# LCD-IDC_Adapter.net
KiCad netlist of a schematic drawn in EAGLE
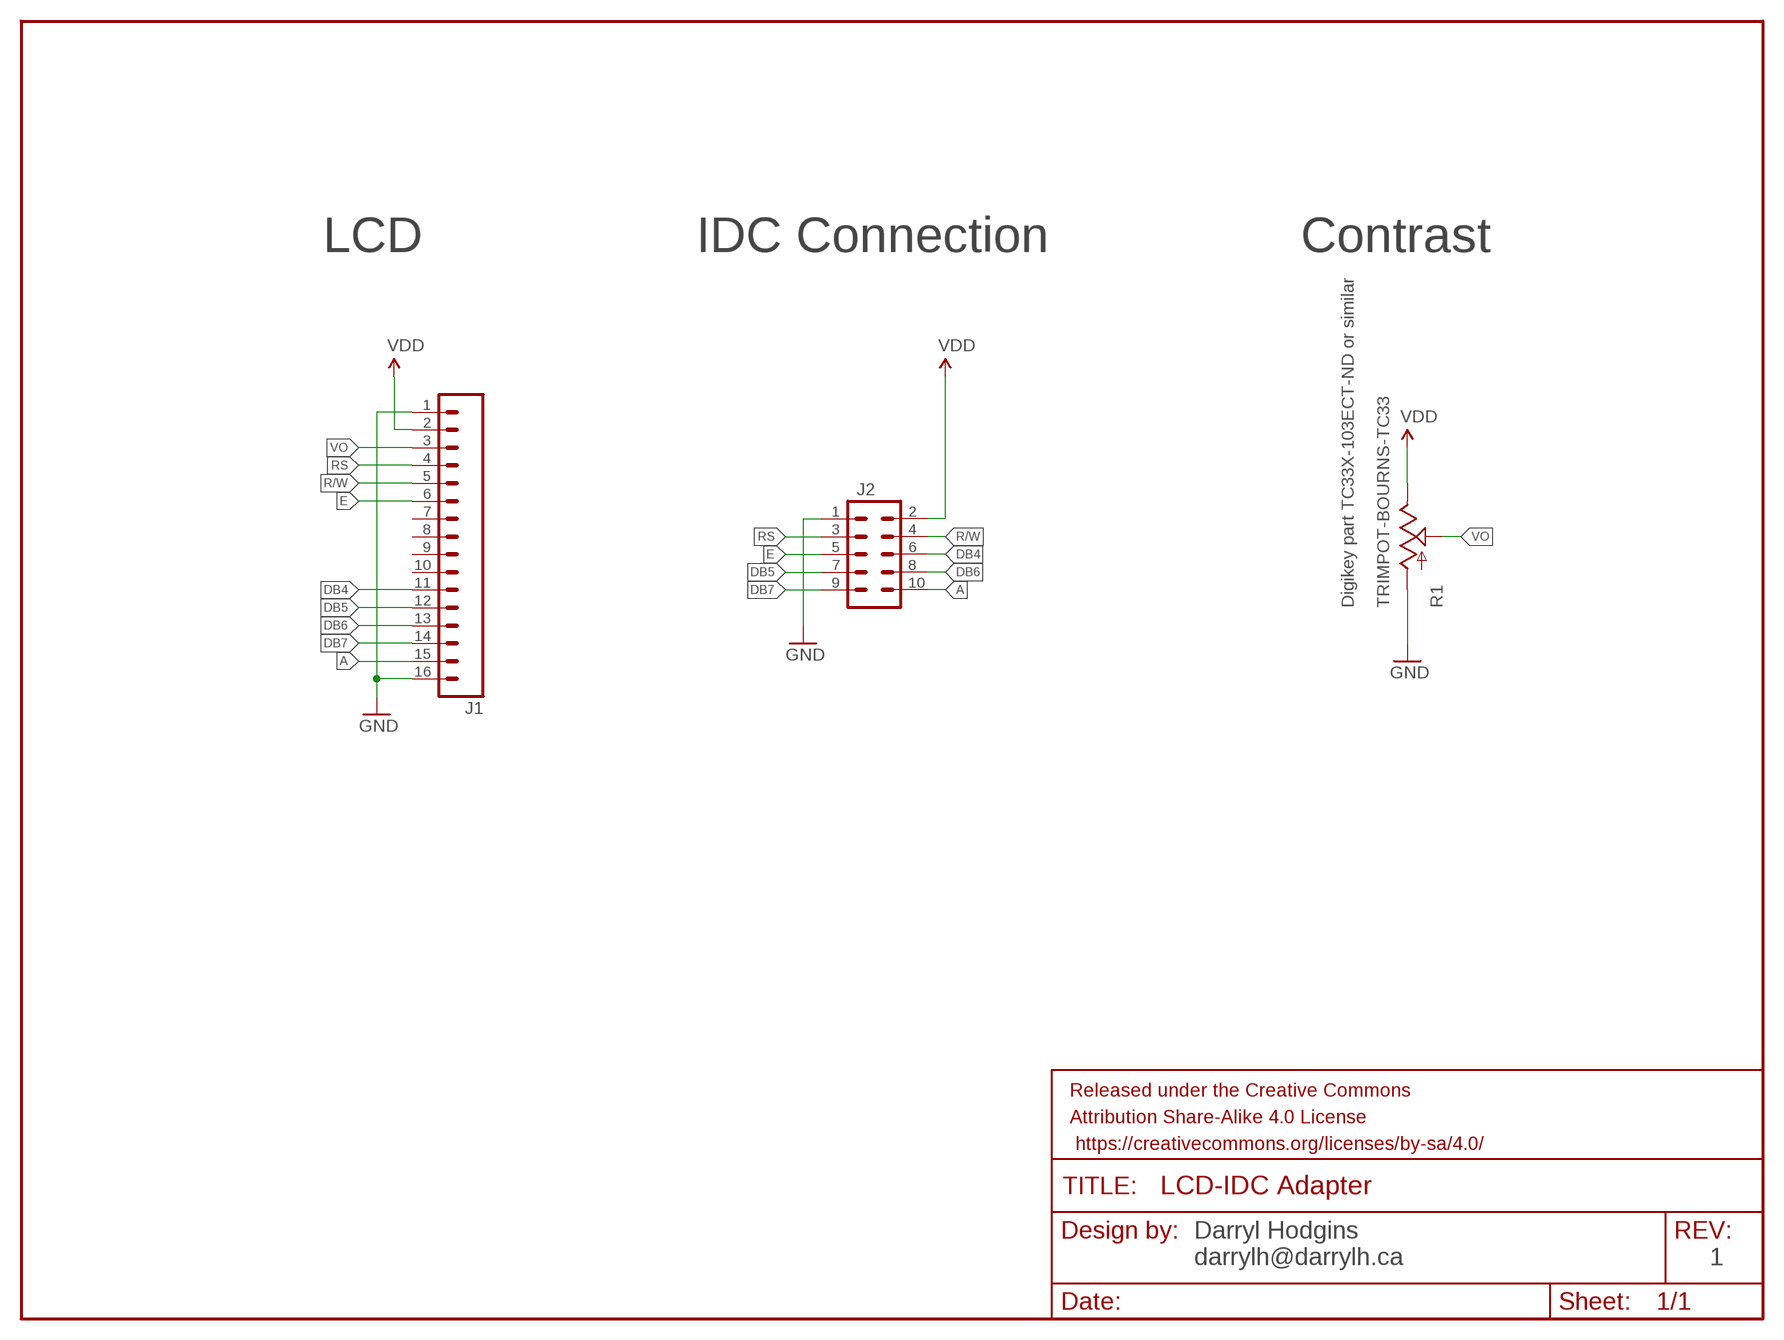
[diagram p0: schematic, sheet 1]

(export (version "E")
  (design (tool "Eeschema 10.0.6"))
  (components
    (comp (ref "FRAME1")
      (value "FRAME-LETTER")
      (footprint "eagle-import:CREATIVE_COMMONS")
      (libsource (lib "eagle-import") (part "FRAME-LETTER"))
    )
    (comp (ref "J1")
      (value "M16PTH")
      (footprint "eagle-import:1X16")
      (libsource (lib "eagle-import") (part "M16PTH"))
    )
    (comp (ref "J2")
      (value "M05X2SHD")
      (footprint "eagle-import:2X5-SHROUDED")
      (libsource (lib "eagle-import") (part "M05X2SHD"))
    )
    (comp (ref "R1")
      (value "TRIMPOT-BOURNS-TC33")
      (footprint "eagle-import:TRIMPOT-BOURNS-TC33")
      (libsource (lib "eagle-import") (part "TRIMPOT-BOURNS-TC33"))
    )
  )
  (nets
    (net (code "1") (name "A") (class "Default")
      (node (ref "J1") (pin "15") (pinfunction "15_15") (pintype "passive"))
      (node (ref "J2") (pin "10") (pinfunction "10_10") (pintype "passive"))
    )
    (net (code "2") (name "DB4") (class "Default")
      (node (ref "J1") (pin "11") (pinfunction "11_11") (pintype "passive"))
      (node (ref "J2") (pin "6") (pinfunction "6_6") (pintype "passive"))
    )
    (net (code "3") (name "DB5") (class "Default")
      (node (ref "J1") (pin "12") (pinfunction "12_12") (pintype "passive"))
      (node (ref "J2") (pin "7") (pinfunction "7_7") (pintype "passive"))
    )
    (net (code "4") (name "DB6") (class "Default")
      (node (ref "J1") (pin "13") (pinfunction "13_13") (pintype "passive"))
      (node (ref "J2") (pin "8") (pinfunction "8_8") (pintype "passive"))
    )
    (net (code "5") (name "DB7") (class "Default")
      (node (ref "J1") (pin "14") (pinfunction "14_14") (pintype "passive"))
      (node (ref "J2") (pin "9") (pinfunction "9_9") (pintype "passive"))
    )
    (net (code "6") (name "E") (class "Default")
      (node (ref "J1") (pin "6") (pinfunction "6_6") (pintype "passive"))
      (node (ref "J2") (pin "5") (pinfunction "5_5") (pintype "passive"))
    )
    (net (code "7") (name "GND") (class "Default")
      (node (ref "J1") (pin "1") (pinfunction "1_1") (pintype "passive"))
      (node (ref "J1") (pin "16") (pinfunction "16_16") (pintype "passive"))
      (node (ref "J2") (pin "1") (pinfunction "1_1") (pintype "passive"))
      (node (ref "R1") (pin "1") (pinfunction "A_1") (pintype "passive"))
    )
    (net (code "8") (name "RS") (class "Default")
      (node (ref "J1") (pin "4") (pinfunction "4_4") (pintype "passive"))
      (node (ref "J2") (pin "3") (pinfunction "3_3") (pintype "passive"))
    )
    (net (code "9") (name "R{slash}W") (class "Default")
      (node (ref "J1") (pin "5") (pinfunction "5_5") (pintype "passive"))
      (node (ref "J2") (pin "4") (pinfunction "4_4") (pintype "passive"))
    )
    (net (code "10") (name "VDD") (class "Default")
      (node (ref "J1") (pin "2") (pinfunction "2_2") (pintype "passive"))
      (node (ref "J2") (pin "2") (pinfunction "2_2") (pintype "passive"))
      (node (ref "R1") (pin "3") (pinfunction "E_3") (pintype "passive"))
    )
    (net (code "11") (name "VO") (class "Default")
      (node (ref "J1") (pin "3") (pinfunction "3_3") (pintype "passive"))
      (node (ref "R1") (pin "2") (pinfunction "S_2") (pintype "passive"))
    )
    (net (code "12") (name "unconnected-(J1-Pad7)") (class "Default")
      (node (ref "J1") (pin "7") (pinfunction "7_7") (pintype "passive"))
    )
    (net (code "13") (name "unconnected-(J1-Pad8)") (class "Default")
      (node (ref "J1") (pin "8") (pinfunction "8_8") (pintype "passive"))
    )
    (net (code "14") (name "unconnected-(J1-Pad9)") (class "Default")
      (node (ref "J1") (pin "9") (pinfunction "9_9") (pintype "passive"))
    )
    (net (code "15") (name "unconnected-(J1-Pad10)") (class "Default")
      (node (ref "J1") (pin "10") (pinfunction "10_10") (pintype "passive"))
    )
  )
)
